# 03_nRF52840_RF.net
KiCad netlist of a schematic drawn in Altium Designer
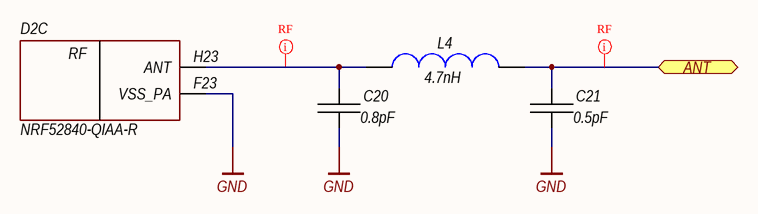
[diagram p0: 03_nRF52840_RF.SchDoc]

(export (version "E")
  (design (tool "Eeschema 10.0.6"))
  (components
    (comp (ref "C20")
      (value "0.8pF")
      (footprint "CAPC1608X09N")
      (description "Ceramic capacitor")
      (fields
        (field (name "MANUFACTURER") "Murata Electronics")
        (field (name "PARTNUMBER") "GQM1875C2ER80BB12D")
      )
      (libsource (lib "Node01") (part "Ceramic"))
    )
    (comp (ref "C21")
      (value "0.5pF")
      (footprint "CAPC1608X09N")
      (description "Ceramic capacitor")
      (fields
        (field (name "MANUFACTURER") "Murata Electronics")
        (field (name "PARTNUMBER") "GQM1875C2ER50WB12D")
      )
      (libsource (lib "Node01") (part "Ceramic"))
    )
    (comp (ref "D2")
      (value "NRF52840-QIAA-R")
      (footprint "AQFN50P700X700X85_HS-74N")
      (description "IC RF TxRx + MCU 802.15.4, Bluetooth Bluetooth v5.0 2.4GHz 73-VFQFN Dual Rows, Exposed Pad")
      (fields (field (name "MANUFACTURER") "Nordic Semiconductor ASA"))
      (libsource (lib "Node01") (part "nRF52840-QFN373"))
    )
    (comp (ref "L4")
      (value "4.7nH")
      (footprint "INDC1608X08N")
      (description "Inductor")
      (fields (field (name "MANUFACTURER") "AVX Corporation") (field (name "PARTNUMBER") "L06034R7CGSTR"))
      (libsource (lib "Node01") (part "Inductor"))
    )
  )
  (nets
    (net (code "1") (name "/ANT") (class "Default")
      (node (ref "C21") (pin "2") (pintype "power_in"))
      (node (ref "L4") (pin "2") (pinfunction "2_2") (pintype "power_in"))
    )
    (net (code "2") (name "GND") (class "Default")
      (node (ref "C20") (pin "1") (pintype "power_in"))
      (node (ref "C21") (pin "1") (pintype "power_in"))
      (node (ref "D2") (pin "F23") (pinfunction "VSS_PA_F23") (pintype "power_in"))
    )
    (net (code "3") (name "Net-(D2C-ANT)") (class "Default")
      (node (ref "C20") (pin "2") (pintype "power_in"))
      (node (ref "D2") (pin "H23") (pinfunction "ANT_H23") (pintype "power_in"))
      (node (ref "L4") (pin "1") (pinfunction "1_1") (pintype "power_in"))
    )
  )
)
